# Swarm_Board.net
KiCad netlist of a schematic drawn in EAGLE
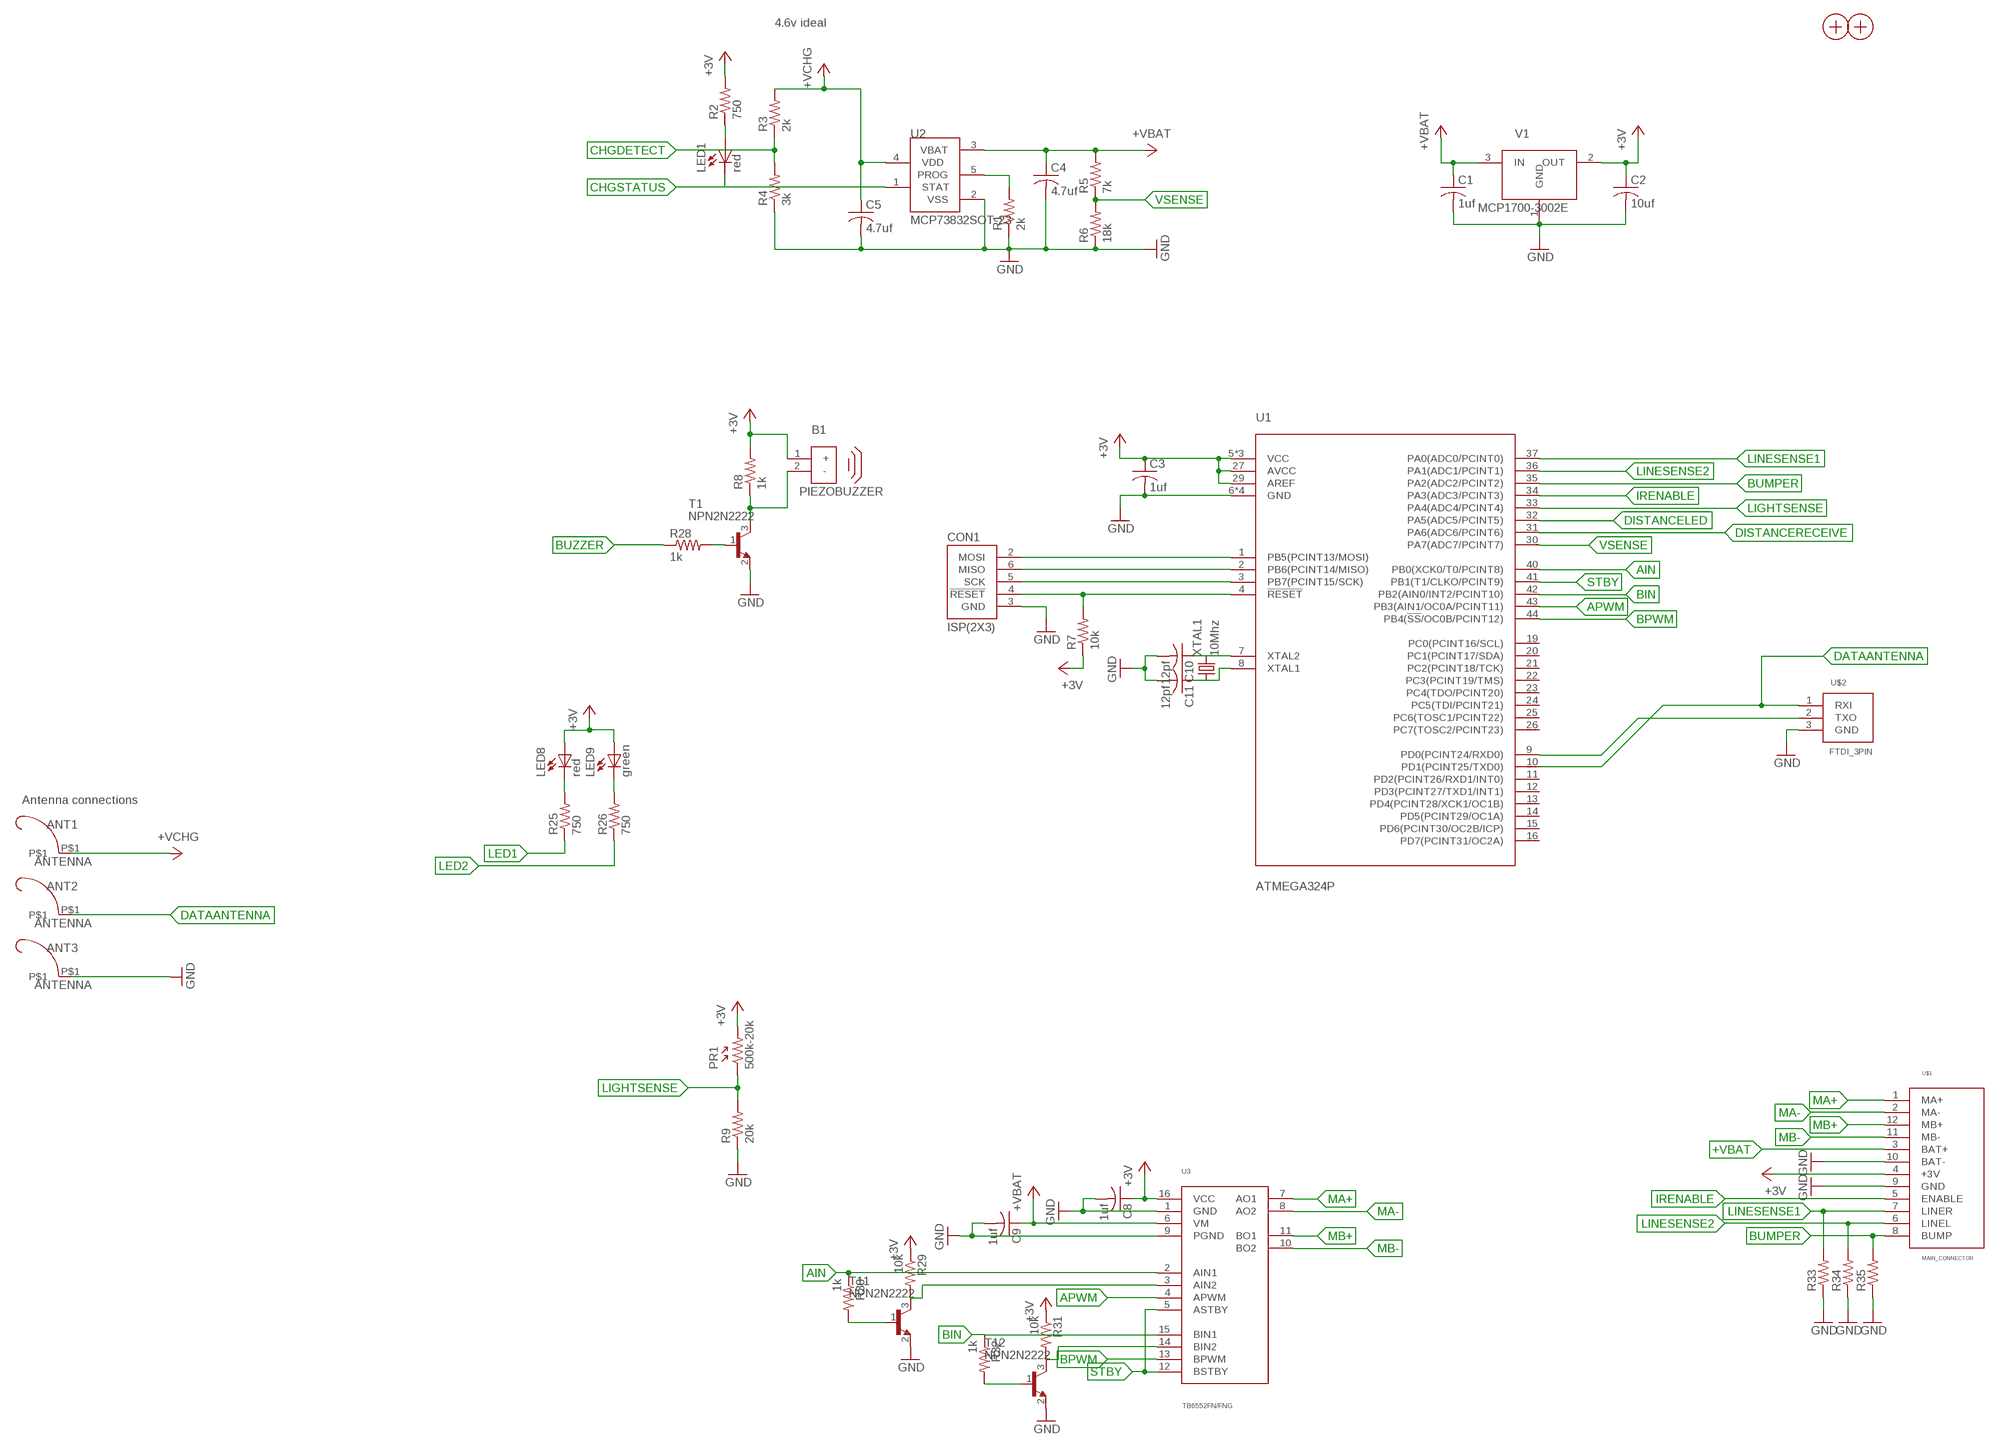
[diagram p0: schematic, sheet 1, part 1 of 2]
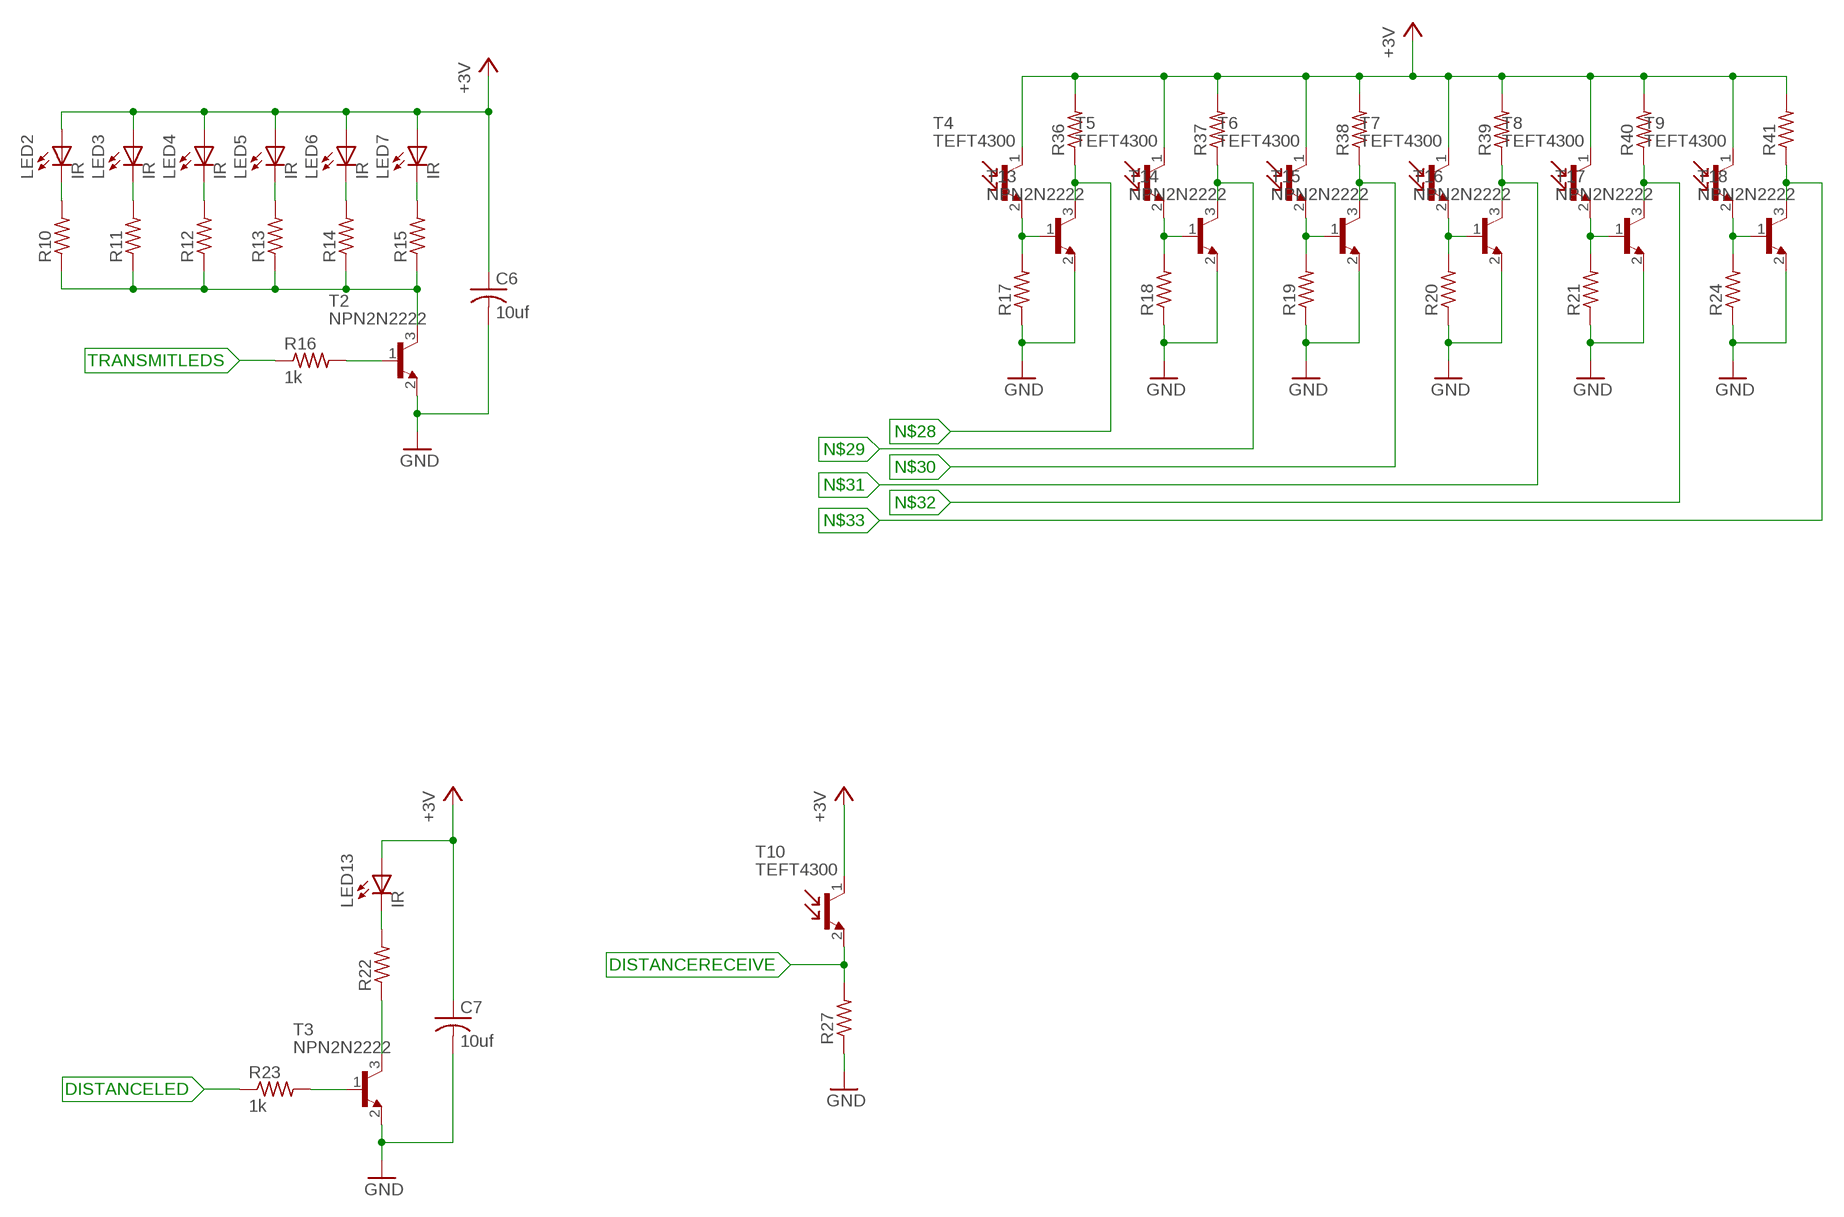
[diagram p1: schematic, sheet 1, part 2 of 2]

(export (version "E")
  (design (tool "Eeschema 10.0.6"))
  (components
    (comp (ref "ANT1")
      (value "ANTENNA")
      (footprint "eagle-import:ANTENNA")
      (libsource (lib "eagle-import") (part "ANTENNA"))
    )
    (comp (ref "ANT2")
      (value "ANTENNA")
      (footprint "eagle-import:ANTENNA")
      (libsource (lib "eagle-import") (part "ANTENNA"))
    )
    (comp (ref "ANT3")
      (value "ANTENNA")
      (footprint "eagle-import:ANTENNA")
      (libsource (lib "eagle-import") (part "ANTENNA"))
    )
    (comp (ref "B1")
      (value "PIEZOBUZZER")
      (footprint "eagle-import:PIEZOBUZZER")
      (libsource (lib "eagle-import") (part "PIEZOBUZZER"))
    )
    (comp (ref "C1")
      (value "1uf")
      (footprint "eagle-import:0603")
      (libsource (lib "eagle-import") (part "CAP0603"))
    )
    (comp (ref "C2")
      (value "10uf")
      (footprint "eagle-import:0805")
      (libsource (lib "eagle-import") (part "CAP0805"))
    )
    (comp (ref "C3")
      (value "1uf")
      (footprint "eagle-import:0603")
      (libsource (lib "eagle-import") (part "CAP0603"))
    )
    (comp (ref "C4")
      (value "4.7uf")
      (footprint "eagle-import:0603")
      (libsource (lib "eagle-import") (part "CAP0603"))
    )
    (comp (ref "C5")
      (value "4.7uf")
      (footprint "eagle-import:0603")
      (libsource (lib "eagle-import") (part "CAP0603"))
    )
    (comp (ref "C6")
      (value "10uf")
      (footprint "eagle-import:0805")
      (libsource (lib "eagle-import") (part "CAP0805"))
    )
    (comp (ref "C7")
      (value "10uf")
      (footprint "eagle-import:0805")
      (libsource (lib "eagle-import") (part "CAP0805"))
    )
    (comp (ref "C8")
      (value "1uf")
      (footprint "eagle-import:0603")
      (libsource (lib "eagle-import") (part "CAP0603"))
    )
    (comp (ref "C9")
      (value "1uf")
      (footprint "eagle-import:0603")
      (libsource (lib "eagle-import") (part "CAP0603"))
    )
    (comp (ref "C10")
      (value "12pf")
      (footprint "eagle-import:0603")
      (libsource (lib "eagle-import") (part "CAP0603"))
    )
    (comp (ref "C11")
      (value "12pf")
      (footprint "eagle-import:0603")
      (libsource (lib "eagle-import") (part "CAP0603"))
    )
    (comp (ref "CON1")
      (value "ISP(2X3)")
      (footprint "eagle-import:PINHEADER(2X3)")
      (libsource (lib "eagle-import") (part "ISP(2X3)"))
    )
    (comp (ref "H1")
      (value "MOUNTINGHOLE")
      (footprint "eagle-import:MOUNTINGHOLE")
      (libsource (lib "eagle-import") (part "MOUNTINGHOLE"))
    )
    (comp (ref "H2")
      (value "MOUNTINGHOLE")
      (footprint "eagle-import:MOUNTINGHOLE")
      (libsource (lib "eagle-import") (part "MOUNTINGHOLE"))
    )
    (comp (ref "LED1")
      (value "red")
      (footprint "eagle-import:0603")
      (libsource (lib "eagle-import") (part "LED0603"))
    )
    (comp (ref "LED2")
      (value "IR")
      (footprint "eagle-import:5MM_LED_RA")
      (libsource (lib "eagle-import") (part "LED5MMRA"))
    )
    (comp (ref "LED3")
      (value "IR")
      (footprint "eagle-import:5MM_LED_RA")
      (libsource (lib "eagle-import") (part "LED5MMRA"))
    )
    (comp (ref "LED4")
      (value "IR")
      (footprint "eagle-import:5MM_LED_RA")
      (libsource (lib "eagle-import") (part "LED5MMRA"))
    )
    (comp (ref "LED5")
      (value "IR")
      (footprint "eagle-import:5MM_LED_RA")
      (libsource (lib "eagle-import") (part "LED5MMRA"))
    )
    (comp (ref "LED6")
      (value "IR")
      (footprint "eagle-import:5MM_LED_RA")
      (libsource (lib "eagle-import") (part "LED5MMRA"))
    )
    (comp (ref "LED7")
      (value "IR")
      (footprint "eagle-import:5MM_LED_RA")
      (libsource (lib "eagle-import") (part "LED5MMRA"))
    )
    (comp (ref "LED8")
      (value "red")
      (footprint "eagle-import:0603")
      (libsource (lib "eagle-import") (part "LED0603"))
    )
    (comp (ref "LED9")
      (value "green")
      (footprint "eagle-import:0603")
      (libsource (lib "eagle-import") (part "LED0603"))
    )
    (comp (ref "LED13")
      (value "IR")
      (footprint "eagle-import:5MM_LED_RA")
      (libsource (lib "eagle-import") (part "LED5MMRA"))
    )
    (comp (ref "PR1")
      (value "500k-20k")
      (footprint "eagle-import:CDSPHOTOCELL")
      (libsource (lib "eagle-import") (part "CDSPHOTORESISTOR"))
    )
    (comp (ref "R1")
      (value "2k")
      (footprint "eagle-import:0603")
      (libsource (lib "eagle-import") (part "RES0603"))
    )
    (comp (ref "R2")
      (value "750")
      (footprint "eagle-import:0603")
      (libsource (lib "eagle-import") (part "RES0603"))
    )
    (comp (ref "R3")
      (value "2k")
      (footprint "eagle-import:0603")
      (libsource (lib "eagle-import") (part "RES0603"))
    )
    (comp (ref "R4")
      (value "3k")
      (footprint "eagle-import:0603")
      (libsource (lib "eagle-import") (part "RES0603"))
    )
    (comp (ref "R5")
      (value "7k")
      (footprint "eagle-import:0603")
      (libsource (lib "eagle-import") (part "RES0603"))
    )
    (comp (ref "R6")
      (value "18k")
      (footprint "eagle-import:0603")
      (libsource (lib "eagle-import") (part "RES0603"))
    )
    (comp (ref "R7")
      (value "10k")
      (footprint "eagle-import:0603")
      (libsource (lib "eagle-import") (part "RES0603"))
    )
    (comp (ref "R8")
      (value "1k")
      (footprint "eagle-import:0603")
      (libsource (lib "eagle-import") (part "RES0603"))
    )
    (comp (ref "R9")
      (value "20k")
      (footprint "eagle-import:0603")
      (libsource (lib "eagle-import") (part "RES0603"))
    )
    (comp (ref "R10")
      (value "RES0603")
      (footprint "eagle-import:0603")
      (libsource (lib "eagle-import") (part "RES0603"))
    )
    (comp (ref "R11")
      (value "RES0603")
      (footprint "eagle-import:0603")
      (libsource (lib "eagle-import") (part "RES0603"))
    )
    (comp (ref "R12")
      (value "RES0603")
      (footprint "eagle-import:0603")
      (libsource (lib "eagle-import") (part "RES0603"))
    )
    (comp (ref "R13")
      (value "RES0603")
      (footprint "eagle-import:0603")
      (libsource (lib "eagle-import") (part "RES0603"))
    )
    (comp (ref "R14")
      (value "RES0603")
      (footprint "eagle-import:0603")
      (libsource (lib "eagle-import") (part "RES0603"))
    )
    (comp (ref "R15")
      (value "RES0603")
      (footprint "eagle-import:0603")
      (libsource (lib "eagle-import") (part "RES0603"))
    )
    (comp (ref "R16")
      (value "1k")
      (footprint "eagle-import:0603")
      (libsource (lib "eagle-import") (part "RES0603"))
    )
    (comp (ref "R17")
      (value "RES0603")
      (footprint "eagle-import:0603")
      (libsource (lib "eagle-import") (part "RES0603"))
    )
    (comp (ref "R18")
      (value "RES0603")
      (footprint "eagle-import:0603")
      (libsource (lib "eagle-import") (part "RES0603"))
    )
    (comp (ref "R19")
      (value "RES0603")
      (footprint "eagle-import:0603")
      (libsource (lib "eagle-import") (part "RES0603"))
    )
    (comp (ref "R20")
      (value "RES0603")
      (footprint "eagle-import:0603")
      (libsource (lib "eagle-import") (part "RES0603"))
    )
    (comp (ref "R21")
      (value "RES0603")
      (footprint "eagle-import:0603")
      (libsource (lib "eagle-import") (part "RES0603"))
    )
    (comp (ref "R22")
      (value "RES0603")
      (footprint "eagle-import:0603")
      (libsource (lib "eagle-import") (part "RES0603"))
    )
    (comp (ref "R23")
      (value "1k")
      (footprint "eagle-import:0603")
      (libsource (lib "eagle-import") (part "RES0603"))
    )
    (comp (ref "R24")
      (value "RES0603")
      (footprint "eagle-import:0603")
      (libsource (lib "eagle-import") (part "RES0603"))
    )
    (comp (ref "R25")
      (value "750")
      (footprint "eagle-import:0603")
      (libsource (lib "eagle-import") (part "RES0603"))
    )
    (comp (ref "R26")
      (value "750")
      (footprint "eagle-import:0603")
      (libsource (lib "eagle-import") (part "RES0603"))
    )
    (comp (ref "R27")
      (value "RES0603")
      (footprint "eagle-import:0603")
      (libsource (lib "eagle-import") (part "RES0603"))
    )
    (comp (ref "R28")
      (value "1k")
      (footprint "eagle-import:0603")
      (libsource (lib "eagle-import") (part "RES0603"))
    )
    (comp (ref "R29")
      (value "10k")
      (footprint "eagle-import:0603")
      (libsource (lib "eagle-import") (part "RES0603"))
    )
    (comp (ref "R30")
      (value "1k")
      (footprint "eagle-import:0603")
      (libsource (lib "eagle-import") (part "RES0603"))
    )
    (comp (ref "R31")
      (value "10k")
      (footprint "eagle-import:0603")
      (libsource (lib "eagle-import") (part "RES0603"))
    )
    (comp (ref "R32")
      (value "1k")
      (footprint "eagle-import:0603")
      (libsource (lib "eagle-import") (part "RES0603"))
    )
    (comp (ref "R33")
      (value "RES0603")
      (footprint "eagle-import:0603")
      (libsource (lib "eagle-import") (part "RES0603"))
    )
    (comp (ref "R34")
      (value "RES0603")
      (footprint "eagle-import:0603")
      (libsource (lib "eagle-import") (part "RES0603"))
    )
    (comp (ref "R35")
      (value "RES0603")
      (footprint "eagle-import:0603")
      (libsource (lib "eagle-import") (part "RES0603"))
    )
    (comp (ref "R36")
      (value "RES0603")
      (footprint "eagle-import:0603")
      (libsource (lib "eagle-import") (part "RES0603"))
    )
    (comp (ref "R37")
      (value "RES0603")
      (footprint "eagle-import:0603")
      (libsource (lib "eagle-import") (part "RES0603"))
    )
    (comp (ref "R38")
      (value "RES0603")
      (footprint "eagle-import:0603")
      (libsource (lib "eagle-import") (part "RES0603"))
    )
    (comp (ref "R39")
      (value "RES0603")
      (footprint "eagle-import:0603")
      (libsource (lib "eagle-import") (part "RES0603"))
    )
    (comp (ref "R40")
      (value "RES0603")
      (footprint "eagle-import:0603")
      (libsource (lib "eagle-import") (part "RES0603"))
    )
    (comp (ref "R41")
      (value "RES0603")
      (footprint "eagle-import:0603")
      (libsource (lib "eagle-import") (part "RES0603"))
    )
    (comp (ref "T1")
      (value "NPN2N2222")
      (footprint "eagle-import:SOT23")
      (libsource (lib "eagle-import") (part "NPN2N2222"))
    )
    (comp (ref "T2")
      (value "NPN2N2222")
      (footprint "eagle-import:SOT23")
      (libsource (lib "eagle-import") (part "NPN2N2222"))
    )
    (comp (ref "T3")
      (value "NPN2N2222")
      (footprint "eagle-import:SOT23")
      (libsource (lib "eagle-import") (part "NPN2N2222"))
    )
    (comp (ref "T4")
      (value "TEFT4300")
      (footprint "eagle-import:3MM_LED_RA")
      (libsource (lib "eagle-import") (part "TEFT4300"))
    )
    (comp (ref "T5")
      (value "TEFT4300")
      (footprint "eagle-import:3MM_LED_RA")
      (libsource (lib "eagle-import") (part "TEFT4300"))
    )
    (comp (ref "T6")
      (value "TEFT4300")
      (footprint "eagle-import:3MM_LED_RA")
      (libsource (lib "eagle-import") (part "TEFT4300"))
    )
    (comp (ref "T7")
      (value "TEFT4300")
      (footprint "eagle-import:3MM_LED_RA")
      (libsource (lib "eagle-import") (part "TEFT4300"))
    )
    (comp (ref "T8")
      (value "TEFT4300")
      (footprint "eagle-import:3MM_LED_RA")
      (libsource (lib "eagle-import") (part "TEFT4300"))
    )
    (comp (ref "T9")
      (value "TEFT4300")
      (footprint "eagle-import:3MM_LED_RA")
      (libsource (lib "eagle-import") (part "TEFT4300"))
    )
    (comp (ref "T10")
      (value "TEFT4300")
      (footprint "eagle-import:3MM_LED_RA")
      (libsource (lib "eagle-import") (part "TEFT4300"))
    )
    (comp (ref "T11")
      (value "NPN2N2222")
      (footprint "eagle-import:SOT23")
      (libsource (lib "eagle-import") (part "NPN2N2222"))
    )
    (comp (ref "T12")
      (value "NPN2N2222")
      (footprint "eagle-import:SOT23")
      (libsource (lib "eagle-import") (part "NPN2N2222"))
    )
    (comp (ref "T13")
      (value "NPN2N2222")
      (footprint "eagle-import:SOT23")
      (libsource (lib "eagle-import") (part "NPN2N2222"))
    )
    (comp (ref "T14")
      (value "NPN2N2222")
      (footprint "eagle-import:SOT23")
      (libsource (lib "eagle-import") (part "NPN2N2222"))
    )
    (comp (ref "T15")
      (value "NPN2N2222")
      (footprint "eagle-import:SOT23")
      (libsource (lib "eagle-import") (part "NPN2N2222"))
    )
    (comp (ref "T16")
      (value "NPN2N2222")
      (footprint "eagle-import:SOT23")
      (libsource (lib "eagle-import") (part "NPN2N2222"))
    )
    (comp (ref "T17")
      (value "NPN2N2222")
      (footprint "eagle-import:SOT23")
      (libsource (lib "eagle-import") (part "NPN2N2222"))
    )
    (comp (ref "T18")
      (value "NPN2N2222")
      (footprint "eagle-import:SOT23")
      (libsource (lib "eagle-import") (part "NPN2N2222"))
    )
    (comp (ref "U$1")
      (value "MAIN_CONNECTOR")
      (footprint "eagle-import:FEMALE_HEADER_2MM_2X6")
      (libsource (lib "eagle-import") (part "MAIN_CONNECTOR"))
    )
    (comp (ref "U$2")
      (value "FTDI_3PIN")
      (footprint "eagle-import:3PINHEADER_.100_")
      (libsource (lib "eagle-import") (part "FTDI_3PIN"))
    )
    (comp (ref "U1")
      (value "ATMEGA324P")
      (footprint "eagle-import:TQFP44")
      (libsource (lib "eagle-import") (part "ATMEGA324P"))
    )
    (comp (ref "U2")
      (value "MCP73832SOT-23")
      (footprint "eagle-import:(OT)SOT-23(5PAD)")
      (libsource (lib "eagle-import") (part "MCP73832SOT-23"))
    )
    (comp (ref "U3")
      (value "TB6552FN/FNG")
      (footprint "eagle-import:16SSOP")
      (libsource (lib "eagle-import") (part "TB6552FN/FNG"))
    )
    (comp (ref "V1")
      (value "MCP1700-3002E")
      (footprint "eagle-import:(TT_NB)SOT-23(3PAD)")
      (libsource (lib "eagle-import") (part "MCP1700-3002E"))
    )
    (comp (ref "XTAL1")
      (value "10Mhz")
      (footprint "eagle-import:SMDXTAL")
      (libsource (lib "eagle-import") (part "NX5032GA-10.000000MHZ"))
    )
  )
  (nets
    (net (code "1") (name "+3V") (class "Default")
      (node (ref "B1") (pin "1") (pinfunction "+_1") (pintype "bidirectional"))
      (node (ref "C2") (pin "1") (pinfunction "1_1") (pintype "passive"))
      (node (ref "C3") (pin "1") (pinfunction "1_1") (pintype "passive"))
      (node (ref "C6") (pin "1") (pinfunction "1_1") (pintype "passive"))
      (node (ref "C7") (pin "1") (pinfunction "1_1") (pintype "passive"))
      (node (ref "C8") (pin "1") (pinfunction "1_1") (pintype "passive"))
      (node (ref "LED13") (pin "1") (pinfunction "A_1") (pintype "passive"))
      (node (ref "LED2") (pin "1") (pinfunction "A_1") (pintype "passive"))
      (node (ref "LED3") (pin "1") (pinfunction "A_1") (pintype "passive"))
      (node (ref "LED4") (pin "1") (pinfunction "A_1") (pintype "passive"))
      (node (ref "LED5") (pin "1") (pinfunction "A_1") (pintype "passive"))
      (node (ref "LED6") (pin "1") (pinfunction "A_1") (pintype "passive"))
      (node (ref "LED7") (pin "1") (pinfunction "A_1") (pintype "passive"))
      (node (ref "LED8") (pin "2") (pinfunction "A_2") (pintype "passive"))
      (node (ref "LED9") (pin "2") (pinfunction "A_2") (pintype "passive"))
      (node (ref "PR1") (pin "2") (pinfunction "2_2") (pintype "passive"))
      (node (ref "R2") (pin "2") (pinfunction "2_2") (pintype "passive"))
      (node (ref "R29") (pin "1") (pinfunction "1_1") (pintype "passive"))
      (node (ref "R31") (pin "1") (pinfunction "1_1") (pintype "passive"))
      (node (ref "R36") (pin "2") (pinfunction "2_2") (pintype "passive"))
      (node (ref "R37") (pin "2") (pinfunction "2_2") (pintype "passive"))
      (node (ref "R38") (pin "2") (pinfunction "2_2") (pintype "passive"))
      (node (ref "R39") (pin "2") (pinfunction "2_2") (pintype "passive"))
      (node (ref "R40") (pin "2") (pinfunction "2_2") (pintype "passive"))
      (node (ref "R41") (pin "2") (pinfunction "2_2") (pintype "passive"))
      (node (ref "R7") (pin "1") (pinfunction "1_1") (pintype "passive"))
      (node (ref "R8") (pin "2") (pinfunction "2_2") (pintype "passive"))
      (node (ref "T10") (pin "1") (pinfunction "C_1") (pintype "passive"))
      (node (ref "T4") (pin "1") (pinfunction "C_1") (pintype "passive"))
      (node (ref "T5") (pin "1") (pinfunction "C_1") (pintype "passive"))
      (node (ref "T6") (pin "1") (pinfunction "C_1") (pintype "passive"))
      (node (ref "T7") (pin "1") (pinfunction "C_1") (pintype "passive"))
      (node (ref "T8") (pin "1") (pinfunction "C_1") (pintype "passive"))
      (node (ref "T9") (pin "1") (pinfunction "C_1") (pintype "passive"))
      (node (ref "U$1") (pin "4") (pinfunction "+3V_4") (pintype "bidirectional"))
      (node (ref "U1") (pin "17") (pinfunction "VCC_17") (pintype "bidirectional"))
      (node (ref "U1") (pin "27") (pinfunction "AVCC_27") (pintype "bidirectional"))
      (node (ref "U1") (pin "29") (pinfunction "AREF_29") (pintype "bidirectional"))
      (node (ref "U1") (pin "38") (pinfunction "VCC_38") (pintype "bidirectional"))
      (node (ref "U1") (pin "5") (pinfunction "VCC_5") (pintype "bidirectional"))
      (node (ref "U3") (pin "16") (pinfunction "VCC_16") (pintype "bidirectional"))
      (node (ref "V1") (pin "2") (pinfunction "OUT_2") (pintype "bidirectional"))
    )
    (net (code "2") (name "+VBAT") (class "Default")
      (node (ref "C1") (pin "1") (pinfunction "1_1") (pintype "passive"))
      (node (ref "C4") (pin "1") (pinfunction "1_1") (pintype "passive"))
      (node (ref "C9") (pin "1") (pinfunction "1_1") (pintype "passive"))
      (node (ref "R5") (pin "2") (pinfunction "2_2") (pintype "passive"))
      (node (ref "U$1") (pin "3") (pinfunction "BAT+_3") (pintype "bidirectional"))
      (node (ref "U2") (pin "3") (pinfunction "VBAT_3") (pintype "bidirectional"))
      (node (ref "U3") (pin "6") (pinfunction "VM_6") (pintype "bidirectional"))
      (node (ref "V1") (pin "3") (pinfunction "IN_3") (pintype "bidirectional"))
    )
    (net (code "3") (name "+VCHG") (class "Default")
      (node (ref "ANT1") (pin "P$1") (pinfunction "P$1_P$1") (pintype "bidirectional"))
      (node (ref "C5") (pin "1") (pinfunction "1_1") (pintype "passive"))
      (node (ref "R3") (pin "2") (pinfunction "2_2") (pintype "passive"))
      (node (ref "U2") (pin "4") (pinfunction "VDD_4") (pintype "bidirectional"))
    )
    (net (code "4") (name "AIN") (class "Default")
      (node (ref "R30") (pin "1") (pinfunction "1_1") (pintype "passive"))
      (node (ref "U1") (pin "40") (pinfunction "PB0(XCK0/T0/PCINT8)_40") (pintype "bidirectional"))
      (node (ref "U3") (pin "2") (pinfunction "AIN1_2") (pintype "bidirectional"))
    )
    (net (code "5") (name "APWM") (class "Default")
      (node (ref "U1") (pin "43") (pinfunction "PB3(AIN1/OC0A/PCINT11)_43") (pintype "bidirectional"))
      (node (ref "U3") (pin "4") (pinfunction "APWM_4") (pintype "bidirectional"))
    )
    (net (code "6") (name "BIN") (class "Default")
      (node (ref "R32") (pin "1") (pinfunction "1_1") (pintype "passive"))
      (node (ref "U1") (pin "42") (pinfunction "PB2(AIN0/INT2/PCINT10)_42") (pintype "bidirectional"))
      (node (ref "U3") (pin "15") (pinfunction "BIN1_15") (pintype "bidirectional"))
    )
    (net (code "7") (name "BPWM") (class "Default")
      (node (ref "U1") (pin "44") (pinfunction "PB4(~{SS}/OC0B/PCINT12)_44") (pintype "bidirectional"))
      (node (ref "U3") (pin "13") (pinfunction "BPWM_13") (pintype "bidirectional"))
    )
    (net (code "8") (name "BUMPER") (class "Default")
      (node (ref "R35") (pin "2") (pinfunction "2_2") (pintype "passive"))
      (node (ref "U$1") (pin "8") (pinfunction "BUMP_8") (pintype "bidirectional"))
      (node (ref "U1") (pin "35") (pinfunction "PA2(ADC2/PCINT2)_35") (pintype "bidirectional"))
    )
    (net (code "9") (name "BUZZER") (class "Default")
      (node (ref "R28") (pin "1") (pinfunction "1_1") (pintype "passive"))
    )
    (net (code "10") (name "CHGDETECT") (class "Default")
      (node (ref "R3") (pin "1") (pinfunction "1_1") (pintype "passive"))
      (node (ref "R4") (pin "2") (pinfunction "2_2") (pintype "passive"))
    )
    (net (code "11") (name "CHGSTATUS") (class "Default")
      (node (ref "LED1") (pin "1") (pinfunction "C_1") (pintype "passive"))
      (node (ref "U2") (pin "1") (pinfunction "STAT_1") (pintype "bidirectional"))
    )
    (net (code "12") (name "DATAANTENNA") (class "Default")
      (node (ref "ANT2") (pin "P$1") (pinfunction "P$1_P$1") (pintype "bidirectional"))
      (node (ref "U$2") (pin "1") (pinfunction "RXI_1") (pintype "bidirectional"))
      (node (ref "U1") (pin "10") (pinfunction "PD1(PCINT25/TXD0)_10") (pintype "bidirectional"))
    )
    (net (code "13") (name "DISTANCELED") (class "Default")
      (node (ref "R23") (pin "1") (pinfunction "1_1") (pintype "passive"))
      (node (ref "U1") (pin "32") (pinfunction "PA5(ADC5/PCINT5)_32") (pintype "bidirectional"))
    )
    (net (code "14") (name "DISTANCERECEIVE") (class "Default")
      (node (ref "R27") (pin "2") (pinfunction "2_2") (pintype "passive"))
      (node (ref "T10") (pin "2") (pinfunction "E_2") (pintype "passive"))
      (node (ref "U1") (pin "31") (pinfunction "PA6(ADC6/PCINT6)_31") (pintype "bidirectional"))
    )
    (net (code "15") (name "GND") (class "Default")
      (node (ref "ANT3") (pin "P$1") (pinfunction "P$1_P$1") (pintype "bidirectional"))
      (node (ref "C1") (pin "2") (pinfunction "2_2") (pintype "passive"))
      (node (ref "C10") (pin "2") (pinfunction "2_2") (pintype "passive"))
      (node (ref "C11") (pin "2") (pinfunction "2_2") (pintype "passive"))
      (node (ref "C2") (pin "2") (pinfunction "2_2") (pintype "passive"))
      (node (ref "C3") (pin "2") (pinfunction "2_2") (pintype "passive"))
      (node (ref "C4") (pin "2") (pinfunction "2_2") (pintype "passive"))
      (node (ref "C5") (pin "2") (pinfunction "2_2") (pintype "passive"))
      (node (ref "C6") (pin "2") (pinfunction "2_2") (pintype "passive"))
      (node (ref "C7") (pin "2") (pinfunction "2_2") (pintype "passive"))
      (node (ref "C8") (pin "2") (pinfunction "2_2") (pintype "passive"))
      (node (ref "C9") (pin "2") (pinfunction "2_2") (pintype "passive"))
      (node (ref "CON1") (pin "3") (pinfunction "GND_3") (pintype "bidirectional"))
      (node (ref "R1") (pin "1") (pinfunction "1_1") (pintype "passive"))
      (node (ref "R17") (pin "1") (pinfunction "1_1") (pintype "passive"))
      (node (ref "R18") (pin "1") (pinfunction "1_1") (pintype "passive"))
      (node (ref "R19") (pin "1") (pinfunction "1_1") (pintype "passive"))
      (node (ref "R20") (pin "1") (pinfunction "1_1") (pintype "passive"))
      (node (ref "R21") (pin "1") (pinfunction "1_1") (pintype "passive"))
      (node (ref "R24") (pin "1") (pinfunction "1_1") (pintype "passive"))
      (node (ref "R27") (pin "1") (pinfunction "1_1") (pintype "passive"))
      (node (ref "R33") (pin "1") (pinfunction "1_1") (pintype "passive"))
      (node (ref "R34") (pin "1") (pinfunction "1_1") (pintype "passive"))
      (node (ref "R35") (pin "1") (pinfunction "1_1") (pintype "passive"))
      (node (ref "R4") (pin "1") (pinfunction "1_1") (pintype "passive"))
      (node (ref "R6") (pin "1") (pinfunction "1_1") (pintype "passive"))
      (node (ref "R9") (pin "1") (pinfunction "1_1") (pintype "passive"))
      (node (ref "T1") (pin "2") (pinfunction "E_2") (pintype "passive"))
      (node (ref "T11") (pin "2") (pinfunction "E_2") (pintype "passive"))
      (node (ref "T12") (pin "2") (pinfunction "E_2") (pintype "passive"))
      (node (ref "T13") (pin "2") (pinfunction "E_2") (pintype "passive"))
      (node (ref "T14") (pin "2") (pinfunction "E_2") (pintype "passive"))
      (node (ref "T15") (pin "2") (pinfunction "E_2") (pintype "passive"))
      (node (ref "T16") (pin "2") (pinfunction "E_2") (pintype "passive"))
      (node (ref "T17") (pin "2") (pinfunction "E_2") (pintype "passive"))
      (node (ref "T18") (pin "2") (pinfunction "E_2") (pintype "passive"))
      (node (ref "T2") (pin "2") (pinfunction "E_2") (pintype "passive"))
      (node (ref "T3") (pin "2") (pinfunction "E_2") (pintype "passive"))
      (node (ref "U$1") (pin "10") (pinfunction "BAT-_10") (pintype "bidirectional"))
      (node (ref "U$1") (pin "9") (pinfunction "GND_9") (pintype "bidirectional"))
      (node (ref "U$2") (pin "3") (pinfunction "GND_3") (pintype "bidirectional"))
      (node (ref "U1") (pin "18") (pinfunction "GND_18") (pintype "bidirectional"))
      (node (ref "U1") (pin "28") (pinfunction "GND_28") (pintype "bidirectional"))
      (node (ref "U1") (pin "39") (pinfunction "GND_39") (pintype "bidirectional"))
      (node (ref "U1") (pin "6") (pinfunction "GND_6") (pintype "bidirectional"))
      (node (ref "U2") (pin "2") (pinfunction "VSS_2") (pintype "bidirectional"))
      (node (ref "U3") (pin "1") (pinfunction "GND_1") (pintype "bidirectional"))
      (node (ref "U3") (pin "9") (pinfunction "PGND_9") (pintype "bidirectional"))
      (node (ref "V1") (pin "1") (pinfunction "GND_1") (pintype "bidirectional"))
    )
    (net (code "16") (name "IRENABLE") (class "Default")
      (node (ref "U$1") (pin "5") (pinfunction "ENABLE_5") (pintype "bidirectional"))
      (node (ref "U1") (pin "34") (pinfunction "PA3(ADC3/PCINT3)_34") (pintype "bidirectional"))
    )
    (net (code "17") (name "LED1") (class "Default")
      (node (ref "R25") (pin "1") (pinfunction "1_1") (pintype "passive"))
    )
    (net (code "18") (name "LED2") (class "Default")
      (node (ref "R26") (pin "1") (pinfunction "1_1") (pintype "passive"))
    )
    (net (code "19") (name "LIGHTSENSE") (class "Default")
      (node (ref "PR1") (pin "1") (pinfunction "1_1") (pintype "passive"))
      (node (ref "R9") (pin "2") (pinfunction "2_2") (pintype "passive"))
      (node (ref "U1") (pin "33") (pinfunction "PA4(ADC4/PCINT4)_33") (pintype "bidirectional"))
    )
    (net (code "20") (name "LINESENSE1") (class "Default")
      (node (ref "R33") (pin "2") (pinfunction "2_2") (pintype "passive"))
      (node (ref "U$1") (pin "7") (pinfunction "LINER_7") (pintype "bidirectional"))
      (node (ref "U1") (pin "37") (pinfunction "PA0(ADC0/PCINT0)_37") (pintype "bidirectional"))
    )
    (net (code "21") (name "LINESENSE2") (class "Default")
      (node (ref "R34") (pin "2") (pinfunction "2_2") (pintype "passive"))
      (node (ref "U$1") (pin "6") (pinfunction "LINEL_6") (pintype "bidirectional"))
      (node (ref "U1") (pin "36") (pinfunction "PA1(ADC1/PCINT1)_36") (pintype "bidirectional"))
    )
    (net (code "22") (name "MA+") (class "Default")
      (node (ref "U$1") (pin "1") (pinfunction "MA+_1") (pintype "bidirectional"))
      (node (ref "U3") (pin "7") (pinfunction "AO1_7") (pintype "bidirectional"))
    )
    (net (code "23") (name "MA-") (class "Default")
      (node (ref "U$1") (pin "2") (pinfunction "MA-_2") (pintype "bidirectional"))
      (node (ref "U3") (pin "8") (pinfunction "AO2_8") (pintype "bidirectional"))
    )
    (net (code "24") (name "MB+") (class "Default")
      (node (ref "U$1") (pin "12") (pinfunction "MB+_12") (pintype "bidirectional"))
      (node (ref "U3") (pin "11") (pinfunction "BO1_11") (pintype "bidirectional"))
    )
    (net (code "25") (name "MB-") (class "Default")
      (node (ref "U$1") (pin "11") (pinfunction "MB-_11") (pintype "bidirectional"))
      (node (ref "U3") (pin "10") (pinfunction "BO2_10") (pintype "bidirectional"))
    )
    (net (code "26") (name "N$28") (class "Default")
      (node (ref "R36") (pin "1") (pinfunction "1_1") (pintype "passive"))
      (node (ref "T13") (pin "3") (pinfunction "C_3") (pintype "passive"))
    )
    (net (code "27") (name "N$29") (class "Default")
      (node (ref "R37") (pin "1") (pinfunction "1_1") (pintype "passive"))
      (node (ref "T14") (pin "3") (pinfunction "C_3") (pintype "passive"))
    )
    (net (code "28") (name "N$30") (class "Default")
      (node (ref "R38") (pin "1") (pinfunction "1_1") (pintype "passive"))
      (node (ref "T15") (pin "3") (pinfunction "C_3") (pintype "passive"))
    )
    (net (code "29") (name "N$31") (class "Default")
      (node (ref "R39") (pin "1") (pinfunction "1_1") (pintype "passive"))
      (node (ref "T16") (pin "3") (pinfunction "C_3") (pintype "passive"))
    )
    (net (code "30") (name "N$32") (class "Default")
      (node (ref "R40") (pin "1") (pinfunction "1_1") (pintype "passive"))
      (node (ref "T17") (pin "3") (pinfunction "C_3") (pintype "passive"))
    )
    (net (code "31") (name "N$33") (class "Default")
      (node (ref "R41") (pin "1") (pinfunction "1_1") (pintype "passive"))
      (node (ref "T18") (pin "3") (pinfunction "C_3") (pintype "passive"))
    )
    (net (code "32") (name "Net-(B1--)") (class "Default")
      (node (ref "B1") (pin "2") (pinfunction "-_2") (pintype "bidirectional"))
      (node (ref "R8") (pin "1") (pinfunction "1_1") (pintype "passive"))
      (node (ref "T1") (pin "3") (pinfunction "C_3") (pintype "passive"))
    )
    (net (code "33") (name "Net-(CON1-MISO)") (class "Default")
      (node (ref "CON1") (pin "6") (pinfunction "MISO_6") (pintype "bidirectional"))
      (node (ref "U1") (pin "2") (pinfunction "PB6(PCINT14/MISO)_2") (pintype "bidirectional"))
    )
    (net (code "34") (name "Net-(CON1-MOSI)") (class "Default")
      (node (ref "CON1") (pin "2") (pinfunction "MOSI_2") (pintype "bidirectional"))
      (node (ref "U1") (pin "1") (pinfunction "PB5(PCINT13/MOSI)_1") (pintype "bidirectional"))
    )
    (net (code "35") (name "Net-(CON1-SCK)") (class "Default")
      (node (ref "CON1") (pin "5") (pinfunction "SCK_5") (pintype "bidirectional"))
      (node (ref "U1") (pin "3") (pinfunction "PB7(PCINT15/SCK)_3") (pintype "bidirectional"))
    )
    (net (code "36") (name "Net-(CON1-~{RESET})") (class "Default")
      (node (ref "CON1") (pin "4") (pinfunction "~{RESET}_4") (pintype "bidirectional"))
      (node (ref "R7") (pin "2") (pinfunction "2_2") (pintype "passive"))
      (node (ref "U1") (pin "4") (pinfunction "~{RESET}_4") (pintype "bidirectional"))
    )
    (net (code "37") (name "Net-(LED1-A)") (class "Default")
      (node (ref "LED1") (pin "2") (pinfunction "A_2") (pintype "passive"))
      (node (ref "R2") (pin "1") (pinfunction "1_1") (pintype "passive"))
    )
    (net (code "38") (name "Net-(LED2-C)") (class "Default")
      (node (ref "LED2") (pin "2") (pinfunction "C_2") (pintype "passive"))
      (node (ref "R10") (pin "2") (pinfunction "2_2") (pintype "passive"))
    )
    (net (code "39") (name "Net-(LED3-C)") (class "Default")
      (node (ref "LED3") (pin "2") (pinfunction "C_2") (pintype "passive"))
      (node (ref "R11") (pin "2") (pinfunction "2_2") (pintype "passive"))
    )
    (net (code "40") (name "Net-(LED4-C)") (class "Default")
      (node (ref "LED4") (pin "2") (pinfunction "C_2") (pintype "passive"))
      (node (ref "R12") (pin "2") (pinfunction "2_2") (pintype "passive"))
    )
    (net (code "41") (name "Net-(LED5-C)") (class "Default")
      (node (ref "LED5") (pin "2") (pinfunction "C_2") (pintype "passive"))
      (node (ref "R13") (pin "2") (pinfunction "2_2") (pintype "passive"))
    )
    (net (code "42") (name "Net-(LED6-C)") (class "Default")
      (node (ref "LED6") (pin "2") (pinfunction "C_2") (pintype "passive"))
      (node (ref "R14") (pin "2") (pinfunction "2_2") (pintype "passive"))
    )
    (net (code "43") (name "Net-(LED7-C)") (class "Default")
      (node (ref "LED7") (pin "2") (pinfunction "C_2") (pintype "passive"))
      (node (ref "R15") (pin "2") (pinfunction "2_2") (pintype "passive"))
    )
    (net (code "44") (name "Net-(LED8-C)") (class "Default")
      (node (ref "LED8") (pin "1") (pinfunction "C_1") (pintype "passive"))
      (node (ref "R25") (pin "2") (pinfunction "2_2") (pintype "passive"))
    )
    (net (code "45") (name "Net-(LED9-C)") (class "Default")
      (node (ref "LED9") (pin "1") (pinfunction "C_1") (pintype "passive"))
      (node (ref "R26") (pin "2") (pinfunction "2_2") (pintype "passive"))
    )
    (net (code "46") (name "Net-(LED13-C)") (class "Default")
      (node (ref "LED13") (pin "2") (pinfunction "C_2") (pintype "passive"))
      (node (ref "R22") (pin "2") (pinfunction "2_2") (pintype "passive"))
    )
    (net (code "47") (name "Net-(T1-B)") (class "Default")
      (node (ref "R28") (pin "2") (pinfunction "2_2") (pintype "passive"))
      (node (ref "T1") (pin "1") (pinfunction "B_1") (pintype "passive"))
    )
    (net (code "48") (name "Net-(T2-B)") (class "Default")
      (node (ref "R16") (pin "2") (pinfunction "2_2") (pintype "passive"))
      (node (ref "T2") (pin "1") (pinfunction "B_1") (pintype "passive"))
    )
    (net (code "49") (name "Net-(T2-C)") (class "Default")
      (node (ref "R10") (pin "1") (pinfunction "1_1") (pintype "passive"))
      (node (ref "R11") (pin "1") (pinfunction "1_1") (pintype "passive"))
      (node (ref "R12") (pin "1") (pinfunction "1_1") (pintype "passive"))
      (node (ref "R13") (pin "1") (pinfunction "1_1") (pintype "passive"))
      (node (ref "R14") (pin "1") (pinfunction "1_1") (pintype "passive"))
      (node (ref "R15") (pin "1") (pinfunction "1_1") (pintype "passive"))
      (node (ref "T2") (pin "3") (pinfunction "C_3") (pintype "passive"))
    )
    (net (code "50") (name "Net-(T3-B)") (class "Default")
      (node (ref "R23") (pin "2") (pinfunction "2_2") (pintype "passive"))
      (node (ref "T3") (pin "1") (pinfunction "B_1") (pintype "passive"))
    )
    (net (code "51") (name "Net-(T3-C)") (class "Default")
      (node (ref "R22") (pin "1") (pinfunction "1_1") (pintype "passive"))
      (node (ref "T3") (pin "3") (pinfunction "C_3") (pintype "passive"))
    )
    (net (code "52") (name "Net-(T11-B)") (class "Default")
      (node (ref "R30") (pin "2") (pinfunction "2_2") (pintype "passive"))
      (node (ref "T11") (pin "1") (pinfunction "B_1") (pintype "passive"))
    )
    (net (code "53") (name "Net-(T11-C)") (class "Default")
      (node (ref "R29") (pin "2") (pinfunction "2_2") (pintype "passive"))
      (node (ref "T11") (pin "3") (pinfunction "C_3") (pintype "passive"))
      (node (ref "U3") (pin "3") (pinfunction "AIN2_3") (pintype "bidirectional"))
    )
    (net (code "54") (name "Net-(T12-B)") (class "Default")
      (node (ref "R32") (pin "2") (pinfunction "2_2") (pintype "passive"))
      (node (ref "T12") (pin "1") (pinfunction "B_1") (pintype "passive"))
    )
    (net (code "55") (name "Net-(T12-C)") (class "Default")
      (node (ref "R31") (pin "2") (pinfunction "2_2") (pintype "passive"))
      (node (ref "T12") (pin "3") (pinfunction "C_3") (pintype "passive"))
      (node (ref "U3") (pin "14") (pinfunction "BIN2_14") (pintype "bidirectional"))
    )
    (net (code "56") (name "Net-(T13-B)") (class "Default")
      (node (ref "R17") (pin "2") (pinfunction "2_2") (pintype "passive"))
      (node (ref "T13") (pin "1") (pinfunction "B_1") (pintype "passive"))
      (node (ref "T4") (pin "2") (pinfunction "E_2") (pintype "passive"))
    )
    (net (code "57") (name "Net-(T14-B)") (class "Default")
      (node (ref "R18") (pin "2") (pinfunction "2_2") (pintype "passive"))
      (node (ref "T14") (pin "1") (pinfunction "B_1") (pintype "passive"))
      (node (ref "T5") (pin "2") (pinfunction "E_2") (pintype "passive"))
    )
    (net (code "58") (name "Net-(T15-B)") (class "Default")
      (node (ref "R19") (pin "2") (pinfunction "2_2") (pintype "passive"))
      (node (ref "T15") (pin "1") (pinfunction "B_1") (pintype "passive"))
      (node (ref "T6") (pin "2") (pinfunction "E_2") (pintype "passive"))
    )
    (net (code "59") (name "Net-(T16-B)") (class "Default")
      (node (ref "R20") (pin "2") (pinfunction "2_2") (pintype "passive"))
      (node (ref "T16") (pin "1") (pinfunction "B_1") (pintype "passive"))
      (node (ref "T7") (pin "2") (pinfunction "E_2") (pintype "passive"))
    )
    (net (code "60") (name "Net-(T17-B)") (class "Default")
      (node (ref "R21") (pin "2") (pinfunction "2_2") (pintype "passive"))
      (node (ref "T17") (pin "1") (pinfunction "B_1") (pintype "passive"))
      (node (ref "T8") (pin "2") (pinfunction "E_2") (pintype "passive"))
    )
    (net (code "61") (name "Net-(T18-B)") (class "Default")
      (node (ref "R24") (pin "2") (pinfunction "2_2") (pintype "passive"))
      (node (ref "T18") (pin "1") (pinfunction "B_1") (pintype "passive"))
      (node (ref "T9") (pin "2") (pinfunction "E_2") (pintype "passive"))
    )
    (net (code "62") (name "Net-(U$2-TXO)") (class "Default")
      (node (ref "U$2") (pin "2") (pinfunction "TXO_2") (pintype "bidirectional"))
      (node (ref "U1") (pin "9") (pinfunction "PD0(PCINT24/RXD0)_9") (pintype "bidirectional"))
    )
    (net (code "63") (name "Net-(U1-XTAL1)") (class "Default")
      (node (ref "C11") (pin "1") (pinfunction "1_1") (pintype "passive"))
      (node (ref "U1") (pin "8") (pinfunction "XTAL1_8") (pintype "bidirectional"))
      (node (ref "XTAL1") (pin "1") (pinfunction "1_1") (pintype "passive"))
    )
    (net (code "64") (name "Net-(U1-XTAL2)") (class "Default")
      (node (ref "C10") (pin "1") (pinfunction "1_1") (pintype "passive"))
      (node (ref "U1") (pin "7") (pinfunction "XTAL2_7") (pintype "bidirectional"))
      (node (ref "XTAL1") (pin "2") (pinfunction "2_2") (pintype "passive"))
    )
    (net (code "65") (name "Net-(U2-PROG)") (class "Default")
      (node (ref "R1") (pin "2") (pinfunction "2_2") (pintype "passive"))
      (node (ref "U2") (pin "5") (pinfunction "PROG_5") (pintype "bidirectional"))
    )
    (net (code "66") (name "STBY") (class "Default")
      (node (ref "U1") (pin "41") (pinfunction "PB1(T1/CLKO/PCINT9)_41") (pintype "bidirectional"))
      (node (ref "U3") (pin "12") (pinfunction "BSTBY_12") (pintype "bidirectional"))
      (node (ref "U3") (pin "5") (pinfunction "ASTBY_5") (pintype "bidirectional"))
    )
    (net (code "67") (name "TRANSMITLEDS") (class "Default")
      (node (ref "R16") (pin "1") (pinfunction "1_1") (pintype "passive"))
    )
    (net (code "68") (name "VSENSE") (class "Default")
      (node (ref "R5") (pin "1") (pinfunction "1_1") (pintype "passive"))
      (node (ref "R6") (pin "2") (pinfunction "2_2") (pintype "passive"))
      (node (ref "U1") (pin "30") (pinfunction "PA7(ADC7/PCINT7)_30") (pintype "bidirectional"))
    )
    (net (code "69") (name "unconnected-(U1-PC0(PCINT16{slash}SCL)-Pad19)") (class "Default")
      (node (ref "U1") (pin "19") (pinfunction "PC0(PCINT16/SCL)_19") (pintype "bidirectional"))
    )
    (net (code "70") (name "unconnected-(U1-PC1(PCINT17{slash}SDA)-Pad20)") (class "Default")
      (node (ref "U1") (pin "20") (pinfunction "PC1(PCINT17/SDA)_20") (pintype "bidirectional"))
    )
    (net (code "71") (name "unconnected-(U1-PC2(PCINT18{slash}TCK)-Pad21)") (class "Default")
      (node (ref "U1") (pin "21") (pinfunction "PC2(PCINT18/TCK)_21") (pintype "bidirectional"))
    )
    (net (code "72") (name "unconnected-(U1-PC3(PCINT19{slash}TMS)-Pad22)") (class "Default")
      (node (ref "U1") (pin "22") (pinfunction "PC3(PCINT19/TMS)_22") (pintype "bidirectional"))
    )
    (net (code "73") (name "unconnected-(U1-PC4(TDO{slash}PCINT20)-Pad23)") (class "Default")
      (node (ref "U1") (pin "23") (pinfunction "PC4(TDO/PCINT20)_23") (pintype "bidirectional"))
    )
    (net (code "74") (name "unconnected-(U1-PC5(TDI{slash}PCINT21)-Pad24)") (class "Default")
      (node (ref "U1") (pin "24") (pinfunction "PC5(TDI/PCINT21)_24") (pintype "bidirectional"))
    )
    (net (code "75") (name "unconnected-(U1-PC6(TOSC1{slash}PCINT22)-Pad25)") (class "Default")
      (node (ref "U1") (pin "25") (pinfunction "PC6(TOSC1/PCINT22)_25") (pintype "bidirectional"))
    )
    (net (code "76") (name "unconnected-(U1-PC7(TOSC2{slash}PCINT23)-Pad26)") (class "Default")
      (node (ref "U1") (pin "26") (pinfunction "PC7(TOSC2/PCINT23)_26") (pintype "bidirectional"))
    )
    (net (code "77") (name "unconnected-(U1-PD2(PCINT26{slash}RXD1{slash}INT0)-Pad11)") (class "Default")
      (node (ref "U1") (pin "11") (pinfunction "PD2(PCINT26/RXD1/INT0)_11") (pintype "bidirectional"))
    )
    (net (code "78") (name "unconnected-(U1-PD3(PCINT27{slash}TXD1{slash}INT1)-Pad12)") (class "Default")
      (node (ref "U1") (pin "12") (pinfunction "PD3(PCINT27/TXD1/INT1)_12") (pintype "bidirectional"))
    )
    (net (code "79") (name "unconnected-(U1-PD4(PCINT28{slash}XCK1{slash}OC1B)-Pad13)") (class "Default")
      (node (ref "U1") (pin "13") (pinfunction "PD4(PCINT28/XCK1/OC1B)_13") (pintype "bidirectional"))
    )
    (net (code "80") (name "unconnected-(U1-PD5(PCINT29{slash}OC1A)-Pad14)") (class "Default")
      (node (ref "U1") (pin "14") (pinfunction "PD5(PCINT29/OC1A)_14") (pintype "bidirectional"))
    )
    (net (code "81") (name "unconnected-(U1-PD6(PCINT30{slash}OC2B{slash}ICP)-Pad15)") (class "Default")
      (node (ref "U1") (pin "15") (pinfunction "PD6(PCINT30/OC2B/ICP)_15") (pintype "bidirectional"))
    )
    (net (code "82") (name "unconnected-(U1-PD7(PCINT31{slash}OC2A)-Pad16)") (class "Default")
      (node (ref "U1") (pin "16") (pinfunction "PD7(PCINT31/OC2A)_16") (pintype "bidirectional"))
    )
  )
)
